# ProPrj_ExtModule-002_2025-02-19.net
KiCad netlist of a schematic drawn in EasyEDA Pro
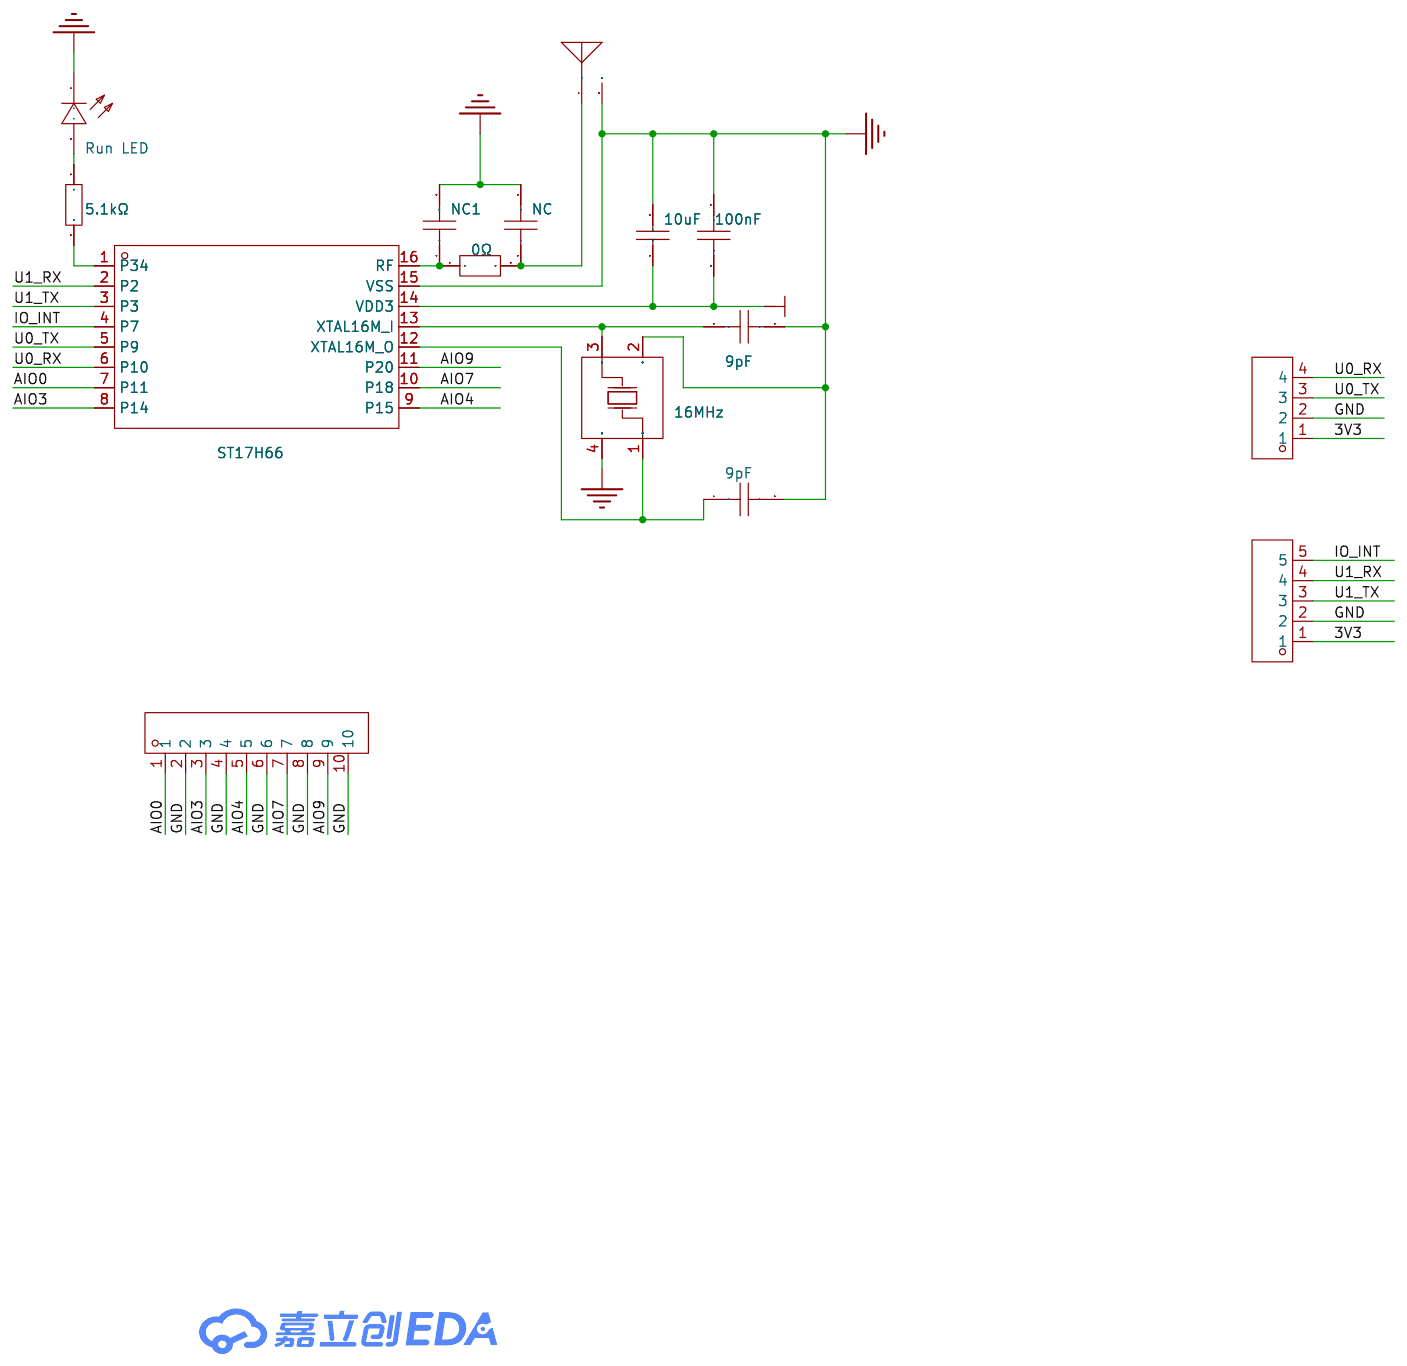
[diagram p0: schematic sheet]

(export (version "E")
  (design (tool "Eeschema 10.0.6"))
  (components
    (comp (ref "C3")
      (value "100nF")
      (footprint "easyedapro:C0402")
      (description "容值:100nF;精度:±10%;额定电压:16V;材质(温度系数):X7R;")
      (fields
        (field (name "Manufacturer Part") "CC0402KRX7R7BB104")
        (field (name "Manufacturer") "YAGEO(国巨)")
      )
      (libsource (lib "easyedapro") (part "CC0402KRX7R7BB104"))
    )
    (comp (ref "C4")
      (value "10uF")
      (footprint "easyedapro:C0402")
      (description "容值:10uF;精度:±20%;额定电压:6.3V;材质(温度系数):X5R;")
      (fields
        (field (name "Manufacturer Part") "CL05A106MQ5NUNC")
        (field (name "Manufacturer") "SAMSUNG(三星)")
      )
      (libsource (lib "easyedapro") (part "CL05A106MQ5NUNC"))
    )
    (comp (ref "C5")
      (value "9pF")
      (footprint "easyedapro:C0402")
      (description "容值:9pF;额定电压:50V;材质(温度系数):C0G;")
      (fields
        (field (name "Manufacturer Part") "GJM1555C1H9R0CB01D")
        (field (name "Manufacturer") "muRata(村田)")
      )
      (libsource (lib "easyedapro") (part "GJM1555C1H9R0CB01D"))
    )
    (comp (ref "C6")
      (value "9pF")
      (footprint "easyedapro:C0402")
      (description "容值:9pF;额定电压:50V;材质(温度系数):C0G;")
      (fields
        (field (name "Manufacturer Part") "GJM1555C1H9R0CB01D")
        (field (name "Manufacturer") "muRata(村田)")
      )
      (libsource (lib "easyedapro") (part "GJM1555C1H9R0CB01D"))
    )
    (comp (ref "H1")
      (value "PZ254V-11-04P")
      (footprint "easyedapro:HDR-TH_4P-P2.54-V-M")
      (fields (field (name "Manufacturer") "XFCN(兴飞)"))
      (libsource (lib "easyedapro") (part "PZ254V-11-04P_C2691448"))
    )
    (comp (ref "H2")
      (value "PZ254V-11-05P")
      (footprint "easyedapro:HDR-TH_5P-P2.54-V-M")
      (fields (field (name "Manufacturer") "XFCN(兴飞)"))
      (libsource (lib "easyedapro") (part "PZ254V-11-05P"))
    )
    (comp (ref "H3")
      (value "PZ254V-11-10P")
      (footprint "easyedapro:HDR-TH_10P-P2.54-V-M")
      (fields (field (name "Manufacturer") "XFCN(兴飞)"))
      (libsource (lib "easyedapro") (part "PZ254V-11-10P"))
    )
    (comp (ref "L1")
      (value "KH-3216-A27")
      (footprint "easyedapro:ANT-SMD_L3.2-W1.6")
      (fields (field (name "Manufacturer") "kinghelm(金航标)"))
      (libsource (lib "easyedapro") (part "KH-3216-A27"))
    )
    (comp (ref "LED2")
      (value "Run LED")
      (footprint "easyedapro:LED0603-RD_RED")
      (fields (field (name "Manufacturer Part") "NCD0603R1") (field (name "Manufacturer") "国星光电"))
      (libsource (lib "easyedapro") (part "FC-DA1608HRK-620D"))
    )
    (comp (ref "NC")
      (value "9pF")
      (footprint "easyedapro:C0402")
      (description "容值:9pF;额定电压:50V;材质(温度系数):NP0;")
      (fields
        (field (name "Manufacturer Part") "CC0402CRNPO9BN9R0")
        (field (name "Manufacturer") "YAGEO(国巨)")
      )
      (libsource (lib "easyedapro") (part "CC0402CRNPO9BN9R0"))
    )
    (comp (ref "NC1")
      (value "9pF")
      (footprint "easyedapro:C0402")
      (description "容值:9pF;额定电压:50V;材质(温度系数):NP0;")
      (fields
        (field (name "Manufacturer Part") "CC0402CRNPO9BN9R0")
        (field (name "Manufacturer") "YAGEO(国巨)")
      )
      (libsource (lib "easyedapro") (part "CC0402CRNPO9BN9R0"))
    )
    (comp (ref "R1")
      (value "0Ω")
      (footprint "easyedapro:R0402")
      (description "电阻类型:厚膜电阻;阻值:0Ω;精度:±5%;功率:62.5mW;最大工作电压:50V;")
      (fields (field (name "Manufacturer Part") "FRC0402P000 TS") (field (name "Manufacturer") "FOJAN(富捷)"))
      (libsource (lib "easyedapro") (part "FRC0402P000 TS"))
    )
    (comp (ref "R18")
      (value "5.1kΩ")
      (footprint "easyedapro:R0402")
      (description "阻值:5.1kΩ;精度:±1%;功率:62.5mW;温度系数:±100ppm/°C;电阻类型:厚膜电阻;")
      (fields
        (field (name "Manufacturer Part") "0402WGF5101TCE")
        (field (name "Manufacturer") "UNI-ROYAL(厚声)")
      )
      (libsource (lib "easyedapro") (part "0402WGF5101TCE"))
    )
    (comp (ref "U1")
      (value "ST17H66")
      (footprint "easyedapro:TSSOP-16_L5.0-W4.4-P0.65-LS6.4-BL")
      (libsource (lib "easyedapro") (part "ST17H66_C9900054761"))
    )
    (comp (ref "X1")
      (value "16MHz")
      (footprint "easyedapro:OSC-SMD_4P-L3.2-W2.5-BL")
      (description "晶振类型:贴片晶振;频率:16MHz;常温频差:±10ppm;外接负载电容:9pF;频率稳定度(全温):±20ppm;")
      (fields (field (name "Manufacturer Part") "X322516MLB4SI") (field (name "Manufacturer") "YXC(扬兴晶振)"))
      (libsource (lib "easyedapro") (part "X322516MLB4SI"))
    )
  )
  (nets
    (net (code "1") (name "/AIO0") (class "Default")
      (node (ref "H3") (pin "1") (pinfunction "1_1") (pintype "unspecified"))
      (node (ref "U1") (pin "7") (pinfunction "P11_7") (pintype "unspecified"))
    )
    (net (code "2") (name "/AIO3") (class "Default")
      (node (ref "H3") (pin "3") (pinfunction "3_3") (pintype "unspecified"))
      (node (ref "U1") (pin "8") (pinfunction "P14_8") (pintype "unspecified"))
    )
    (net (code "3") (name "/AIO4") (class "Default")
      (node (ref "H3") (pin "5") (pinfunction "5_5") (pintype "unspecified"))
      (node (ref "U1") (pin "9") (pinfunction "P15_9") (pintype "unspecified"))
    )
    (net (code "4") (name "/AIO7") (class "Default")
      (node (ref "H3") (pin "7") (pinfunction "7_7") (pintype "unspecified"))
      (node (ref "U1") (pin "10") (pinfunction "P18_10") (pintype "unspecified"))
    )
    (net (code "5") (name "/AIO9") (class "Default")
      (node (ref "H3") (pin "9") (pinfunction "9_9") (pintype "unspecified"))
      (node (ref "U1") (pin "11") (pinfunction "P20_11") (pintype "unspecified"))
    )
    (net (code "6") (name "/IO_INT") (class "Default")
      (node (ref "H2") (pin "5") (pinfunction "5_5") (pintype "unspecified"))
      (node (ref "U1") (pin "4") (pinfunction "P7_4") (pintype "unspecified"))
    )
    (net (code "7") (name "/U0_RX") (class "Default")
      (node (ref "H1") (pin "4") (pinfunction "4_4") (pintype "unspecified"))
      (node (ref "U1") (pin "6") (pinfunction "P10_6") (pintype "unspecified"))
    )
    (net (code "8") (name "/U0_TX") (class "Default")
      (node (ref "H1") (pin "3") (pinfunction "3_3") (pintype "unspecified"))
      (node (ref "U1") (pin "5") (pinfunction "P9_5") (pintype "unspecified"))
    )
    (net (code "9") (name "/U1_RX") (class "Default")
      (node (ref "H2") (pin "4") (pinfunction "4_4") (pintype "unspecified"))
      (node (ref "U1") (pin "2") (pinfunction "P2_2") (pintype "unspecified"))
    )
    (net (code "10") (name "/U1_TX") (class "Default")
      (node (ref "H2") (pin "3") (pinfunction "3_3") (pintype "unspecified"))
      (node (ref "U1") (pin "3") (pinfunction "P3_3") (pintype "unspecified"))
    )
    (net (code "11") (name "3V3") (class "Default")
      (node (ref "C3") (pin "2") (pinfunction "2_2") (pintype "unspecified"))
      (node (ref "C4") (pin "2") (pinfunction "2_2") (pintype "input"))
      (node (ref "H1") (pin "1") (pinfunction "1_1") (pintype "unspecified"))
      (node (ref "H2") (pin "1") (pinfunction "1_1") (pintype "unspecified"))
      (node (ref "U1") (pin "14") (pinfunction "VDD3_14") (pintype "unspecified"))
    )
    (net (code "12") (name "GND") (class "Default")
      (node (ref "C3") (pin "1") (pinfunction "1_1") (pintype "unspecified"))
      (node (ref "C4") (pin "1") (pinfunction "1_1") (pintype "input"))
      (node (ref "C5") (pin "2") (pinfunction "2_2") (pintype "unspecified"))
      (node (ref "C6") (pin "2") (pinfunction "2_2") (pintype "unspecified"))
      (node (ref "H1") (pin "2") (pinfunction "2_2") (pintype "unspecified"))
      (node (ref "H2") (pin "2") (pinfunction "2_2") (pintype "unspecified"))
      (node (ref "H3") (pin "10") (pinfunction "10_10") (pintype "unspecified"))
      (node (ref "H3") (pin "2") (pinfunction "2_2") (pintype "unspecified"))
      (node (ref "H3") (pin "4") (pinfunction "4_4") (pintype "unspecified"))
      (node (ref "H3") (pin "6") (pinfunction "6_6") (pintype "unspecified"))
      (node (ref "H3") (pin "8") (pinfunction "8_8") (pintype "unspecified"))
      (node (ref "L1") (pin "2") (pinfunction "2_2") (pintype "unspecified"))
      (node (ref "LED2") (pin "1") (pinfunction "K_1") (pintype "input"))
      (node (ref "NC") (pin "2") (pinfunction "2_2") (pintype "unspecified"))
      (node (ref "NC1") (pin "2") (pinfunction "2_2") (pintype "unspecified"))
      (node (ref "U1") (pin "15") (pinfunction "VSS_15") (pintype "unspecified"))
      (node (ref "X1") (pin "2") (pinfunction "GND_2") (pintype "unspecified"))
      (node (ref "X1") (pin "4") (pinfunction "GND_4") (pintype "unspecified"))
    )
    (net (code "13") (name "Net-(L1-ANT)") (class "Default")
      (node (ref "L1") (pin "1") (pinfunction "ANT_1") (pintype "unspecified"))
      (node (ref "NC") (pin "1") (pinfunction "1_1") (pintype "unspecified"))
      (node (ref "R1") (pin "2") (pinfunction "2_2") (pintype "unspecified"))
    )
    (net (code "14") (name "Net-(LED2-A)") (class "Default")
      (node (ref "LED2") (pin "2") (pinfunction "A_2") (pintype "input"))
      (node (ref "R18") (pin "1") (pinfunction "1_1") (pintype "input"))
    )
    (net (code "15") (name "Net-(U1-P34)") (class "Default")
      (node (ref "R18") (pin "2") (pinfunction "2_2") (pintype "input"))
      (node (ref "U1") (pin "1") (pinfunction "P34_1") (pintype "unspecified"))
    )
    (net (code "16") (name "Net-(U1-RF)") (class "Default")
      (node (ref "NC1") (pin "1") (pinfunction "1_1") (pintype "unspecified"))
      (node (ref "R1") (pin "1") (pinfunction "1_1") (pintype "unspecified"))
      (node (ref "U1") (pin "16") (pinfunction "RF_16") (pintype "unspecified"))
    )
    (net (code "17") (name "Net-(U1-XTAL16M_I)") (class "Default")
      (node (ref "C5") (pin "1") (pinfunction "1_1") (pintype "unspecified"))
      (node (ref "U1") (pin "13") (pinfunction "XTAL16M_I_13") (pintype "unspecified"))
      (node (ref "X1") (pin "3") (pinfunction "OSC2_3") (pintype "unspecified"))
    )
    (net (code "18") (name "Net-(U1-XTAL16M_O)") (class "Default")
      (node (ref "C6") (pin "1") (pinfunction "1_1") (pintype "unspecified"))
      (node (ref "U1") (pin "12") (pinfunction "XTAL16M_O_12") (pintype "unspecified"))
      (node (ref "X1") (pin "1") (pinfunction "OSC1_1") (pintype "unspecified"))
    )
  )
)
